# trial1.net
KiCad netlist of a schematic drawn in EAGLE
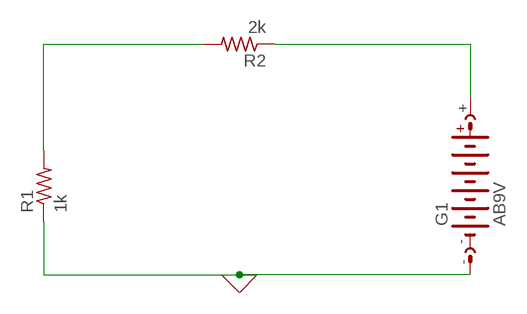
[diagram p0: schematic, sheet 1]

(export (version "E")
  (design (tool "Eeschema 10.0.6"))
  (components
    (comp (ref "G1")
      (value "AB9V")
      (footprint "eagle-import:AB9V")
      (libsource (lib "eagle-import") (part "AB9V"))
    )
    (comp (ref "R1")
      (value "1k")
      (footprint "eagle-import:0204V")
      (libsource (lib "eagle-import") (part "R-US_0204/2V"))
    )
    (comp (ref "R2")
      (value "2k")
      (footprint "eagle-import:0204V")
      (libsource (lib "eagle-import") (part "R-US_0204/2V"))
    )
  )
  (nets
    (net (code "1") (name "GND") (class "Default")
      (node (ref "G1") (pin "-") (pinfunction "-_-") (pintype "passive"))
      (node (ref "R1") (pin "1") (pinfunction "1_1") (pintype "passive"))
    )
    (net (code "2") (name "Net-(G1-Pad+)") (class "Default")
      (node (ref "G1") (pin "+") (pinfunction "+_+") (pintype "passive"))
      (node (ref "R2") (pin "1") (pinfunction "1_1") (pintype "passive"))
    )
    (net (code "3") (name "Net-(R1-Pad2)") (class "Default")
      (node (ref "R1") (pin "2") (pinfunction "2_2") (pintype "passive"))
      (node (ref "R2") (pin "2") (pinfunction "2_2") (pintype "passive"))
    )
  )
)
